# Power.net
KiCad netlist of a schematic drawn in Altium Designer
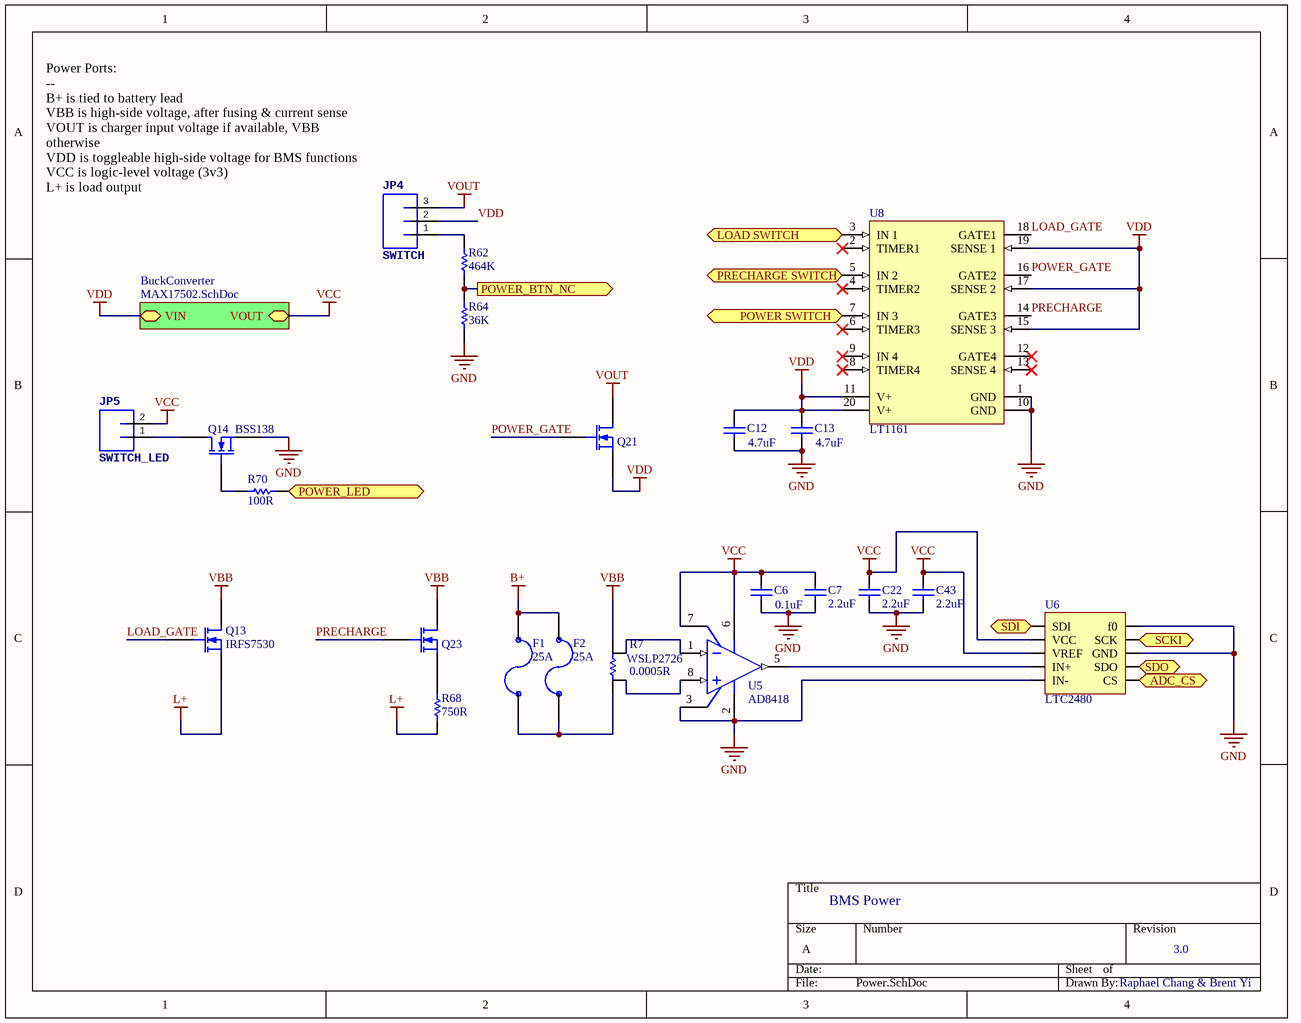
[diagram p0: Power.SchDoc]

(export (version "E")
  (design (tool "Eeschema 10.0.6"))
  (components
    (comp (ref "C6")
      (value "0.1uF")
      (footprint "CAPC0603(1608)55_N")
      (description "CAP 2.2uF 16V Â±10% 0603 (1608 Metric) Thickness 0.55mm SMD")
      (fields (field (name "TOLERANCE") "Â±10%"))
      (libsource (lib "Altium Content Vault") (part "CMP-1035-02762-1"))
    )
    (comp (ref "C7")
      (value "2.2uF")
      (footprint "CAPC0603(1608)100_N")
      (description "CAP 1uF 6.3V Â±10% 0603 (1608 Metric) Thickness 1mm SMD")
      (fields (field (name "TOLERANCE") "Â±10%"))
      (libsource (lib "Altium Content Vault") (part "CMP-1035-02730-1"))
    )
    (comp (ref "C12")
      (value "4.7uF")
      (footprint "CAPC1210(3225)280_N")
      (description "CAP 100uF 10V Â±10% 1210 (3225 Metric) Thickness 2.8mm SMD")
      (fields (field (name "TOLERANCE") "Â±10%"))
      (libsource (lib "Altium Content Vault") (part "CMP-1038-02301-1"))
    )
    (comp (ref "C13")
      (value "4.7uF")
      (footprint "CAPC1210(3225)280_N")
      (description "CAP 100uF 10V Â±10% 1210 (3225 Metric) Thickness 2.8mm SMD")
      (fields (field (name "TOLERANCE") "Â±10%"))
      (libsource (lib "Altium Content Vault") (part "CMP-1038-02301-1"))
    )
    (comp (ref "C22")
      (value "2.2uF")
      (footprint "CAPC0603(1608)55_N")
      (description "CAP 2.2uF 4V Â±10% 0603 (1608 Metric) Thickness 0.55mm SMD")
      (fields (field (name "TOLERANCE") "Â±10%"))
      (libsource (lib "Altium Content Vault") (part "CMP-1035-02751-1"))
    )
    (comp (ref "C43")
      (value "2.2uF")
      (footprint "CAPC0603(1608)55_N")
      (description "CAP 2.2uF 4V Â±10% 0603 (1608 Metric) Thickness 0.55mm SMD")
      (fields (field (name "TOLERANCE") "Â±10%"))
      (libsource (lib "Altium Content Vault") (part "CMP-1035-02751-1"))
    )
    (comp (ref "F1")
      (value "25A")
      (footprint "1206_FUSE")
      (description "Fuse")
      (libsource (lib "Components") (part "FUSE 1206"))
    )
    (comp (ref "F2")
      (value "25A")
      (footprint "1206_FUSE")
      (description "Fuse")
      (libsource (lib "Components") (part "FUSE 1206"))
    )
    (comp (ref "JP4")
      (value "SWITCH")
      (footprint "JST-3-PTH-VERT")
      (libsource (lib "Components") (part "JST_3"))
    )
    (comp (ref "JP5")
      (value "SWITCH_LED")
      (footprint "JST-2-PTH-VERT")
      (libsource (lib "Components") (part "JST_2_VERT"))
    )
    (comp (ref "Q13")
      (value "IRFS7530")
      (footprint "DPAK127P1525X483-7N")
      (description "N-Channel MOSFET")
      (fields (field (name "PUBLISHER") "Altium Limited"))
      (libsource (lib "Components") (part "MOSFET-N"))
    )
    (comp (ref "Q14")
      (value "BSS138")
      (footprint "SOT23-3")
      (description "N-Channel MOSFET")
      (fields (field (name "PUBLISHER") "Altium Limited"))
      (libsource (lib "Components") (part "MOSFET-N"))
    )
    (comp (ref "Q21")
      (value "FDS5672")
      (footprint "SOIC127P600X175-8N")
      (description "N-Channel MOSFET")
      (fields (field (name "PUBLISHER") "Altium Limited"))
      (libsource (lib "Components") (part "MOSFET-N"))
    )
    (comp (ref "Q23")
      (value "BSS138")
      (footprint "SOT23-3")
      (description "N-Channel MOSFET")
      (fields (field (name "PUBLISHER") "Altium Limited"))
      (libsource (lib "Components") (part "MOSFET-N"))
    )
    (comp (ref "R7")
      (value "WSLP2726")
      (footprint "WSL2726")
      (description "Resistor")
      (fields (field (name "ALTIUM_VALUE") "0.0005R") (field (name "PUBLISHER") "Altium Limited"))
      (libsource (lib "Components") (part "WSLP2726"))
    )
    (comp (ref "R62")
      (value "464K")
      (footprint "RESC0603(1608)_L")
      (description "464K 0.1W 1% 0603 (1608 Metric)  SMD")
      (fields (field (name "TOLERANCE") "1 %") (field (name "POWER") "0.1 W"))
      (libsource (lib "Altium Content Vault") (part "CMP-1012-00811-1"))
    )
    (comp (ref "R64")
      (value "36K")
      (footprint "RESC0603(1608)_L")
      (description "36K 0.1W 1% 0603 (1608 Metric)  SMD")
      (fields (field (name "POWER") "0.1 W") (field (name "TOLERANCE") "1 %"))
      (libsource (lib "Altium Content Vault") (part "CMP-1012-00685-1"))
    )
    (comp (ref "R68")
      (value "750R")
      (footprint "RESC2512(6432)_N")
      (description "750R 1W 1% 2512 (6432 Metric)  SMD")
      (fields (field (name "TOLERANCE") "1 %") (field (name "POWER") "1 W"))
      (libsource (lib "Altium Content Vault") (part "RES"))
    )
    (comp (ref "R70")
      (value "100R")
      (footprint "RESC0603(1608)_L")
      (description "100R 0.1W 5% 0603 (1608 Metric)  SMD")
      (fields (field (name "TOLERANCE") "5 %") (field (name "POWER") "0.1 W"))
      (libsource (lib "Altium Content Vault") (part "CMP-1012-00050-1"))
    )
    (comp (ref "U5") (value "AD8418") (footprint "MSOP-8") (libsource (lib "Components") (part "AD8418")))
    (comp (ref "U6") (value "LTC2480") (footprint "MSOP10") (libsource (lib "Components") (part "LTC2480")))
    (comp (ref "U8")
      (value "LT1161")
      (footprint "LT-SW-20_M")
      (fields (field (name "MANUFACTURER") "Linear Technology") (field (name "PARTNUMBER") "LT1161ISW#PBF"))
      (libsource (lib "Altium Inc") (part "LT-LT1161-20"))
    )
  )
  (nets
    (net (code "1") (name "/ADC_CS") (class "Default")
      (node (ref "U6") (pin "9") (pinfunction "CS_9") (pintype "passive"))
    )
    (net (code "2") (name "/LOAD SWITCH") (class "Default")
      (node (ref "U8") (pin "3") (pinfunction "IN_1_3") (pintype "input"))
    )
    (net (code "3") (name "/LOAD_GATE") (class "Default")
      (node (ref "Q13") (pin "1") (pinfunction "G_1") (pintype "passive"))
      (node (ref "U8") (pin "18") (pinfunction "GATE1_18") (pintype "tri_state"))
    )
    (net (code "4") (name "/POWER SWITCH") (class "Default")
      (node (ref "U8") (pin "7") (pinfunction "IN_3_7") (pintype "input"))
    )
    (net (code "5") (name "/POWER_BTN_NC") (class "Default")
      (node (ref "R62") (pin "1") (pinfunction "1_1") (pintype "passive"))
      (node (ref "R64") (pin "2") (pinfunction "2_2") (pintype "passive"))
    )
    (net (code "6") (name "/POWER_GATE") (class "Default")
      (node (ref "Q21") (pin "1") (pinfunction "G_1") (pintype "passive"))
      (node (ref "U8") (pin "16") (pinfunction "GATE2_16") (pintype "tri_state"))
    )
    (net (code "7") (name "/POWER_LED") (class "Default")
      (node (ref "R70") (pin "1") (pinfunction "1_1") (pintype "passive"))
    )
    (net (code "8") (name "/PRECHARGE") (class "Default")
      (node (ref "Q23") (pin "1") (pinfunction "G_1") (pintype "passive"))
      (node (ref "U8") (pin "14") (pinfunction "GATE3_14") (pintype "tri_state"))
    )
    (net (code "9") (name "/PRECHARGE SWITCH") (class "Default")
      (node (ref "U8") (pin "5") (pinfunction "IN_2_5") (pintype "input"))
    )
    (net (code "10") (name "/SCKI") (class "Default")
      (node (ref "U6") (pin "6") (pinfunction "SCK_6") (pintype "passive"))
    )
    (net (code "11") (name "/SDI") (class "Default")
      (node (ref "U6") (pin "0") (pinfunction "SDI_0") (pintype "passive"))
    )
    (net (code "12") (name "/SDO") (class "Default")
      (node (ref "U6") (pin "8") (pinfunction "SDO_8") (pintype "passive"))
    )
    (net (code "13") (name "B+") (class "Default")
      (node (ref "F1") (pin "1") (pinfunction "1_1") (pintype "passive"))
      (node (ref "F2") (pin "1") (pinfunction "1_1") (pintype "passive"))
    )
    (net (code "14") (name "GND") (class "Default")
      (node (ref "C12") (pin "1") (pinfunction "1_1") (pintype "passive"))
      (node (ref "C13") (pin "1") (pinfunction "1_1") (pintype "passive"))
      (node (ref "C22") (pin "1") (pinfunction "1_1") (pintype "passive"))
      (node (ref "C43") (pin "1") (pinfunction "1_1") (pintype "passive"))
      (node (ref "C6") (pin "2") (pinfunction "2_2") (pintype "passive"))
      (node (ref "C7") (pin "2") (pinfunction "2_2") (pintype "passive"))
      (node (ref "Q14") (pin "3") (pinfunction "S_3") (pintype "passive"))
      (node (ref "R64") (pin "1") (pinfunction "1_1") (pintype "passive"))
      (node (ref "U5") (pin "2") (pinfunction "GND_2") (pintype "power_in"))
      (node (ref "U5") (pin "3") (pinfunction "VREF2_3") (pintype "passive"))
      (node (ref "U6") (pin "4") (pinfunction "IN-_4") (pintype "passive"))
      (node (ref "U6") (pin "5") (pinfunction "f0_5") (pintype "passive"))
      (node (ref "U6") (pin "7") (pinfunction "GND_7") (pintype "passive"))
      (node (ref "U8") (pin "1") (pinfunction "GND_1") (pintype "power_in"))
      (node (ref "U8") (pin "10") (pinfunction "GND_10") (pintype "power_in"))
    )
    (net (code "15") (name "L+") (class "Default")
      (node (ref "Q13") (pin "3") (pinfunction "S_3") (pintype "passive"))
      (node (ref "R68") (pin "1") (pinfunction "1_1") (pintype "passive"))
    )
    (net (code "16") (name "Net-(F1-Pad2)") (class "Default")
      (node (ref "F1") (pin "2") (pinfunction "2_2") (pintype "passive"))
      (node (ref "F2") (pin "2") (pinfunction "2_2") (pintype "passive"))
      (node (ref "R7") (pin "1") (pinfunction "1_1") (pintype "passive"))
    )
    (net (code "17") (name "Net-(JP4-Pad1)") (class "Default")
      (node (ref "JP4") (pin "1") (pinfunction "1_1") (pintype "passive"))
      (node (ref "R62") (pin "2") (pinfunction "2_2") (pintype "passive"))
    )
    (net (code "18") (name "Net-(Q14-D)") (class "Default")
      (node (ref "JP5") (pin "1") (pinfunction "1_1") (pintype "passive"))
      (node (ref "Q14") (pin "2") (pinfunction "D_2") (pintype "passive"))
    )
    (net (code "19") (name "Net-(Q14-G)") (class "Default")
      (node (ref "Q14") (pin "1") (pinfunction "G_1") (pintype "passive"))
      (node (ref "R70") (pin "2") (pinfunction "2_2") (pintype "passive"))
    )
    (net (code "20") (name "Net-(Q23-S)") (class "Default")
      (node (ref "Q23") (pin "3") (pinfunction "S_3") (pintype "passive"))
      (node (ref "R68") (pin "2") (pinfunction "2_2") (pintype "passive"))
    )
    (net (code "21") (name "Net-(U5-IN+)") (class "Default")
      (node (ref "R7") (pin "3") (pinfunction "3_3") (pintype "passive"))
      (node (ref "U5") (pin "8") (pinfunction "IN+_8") (pintype "input"))
    )
    (net (code "22") (name "Net-(U5-IN-)") (class "Default")
      (node (ref "R7") (pin "4") (pinfunction "4_4") (pintype "passive"))
      (node (ref "U5") (pin "1") (pinfunction "IN-_1") (pintype "input"))
    )
    (net (code "23") (name "Net-(U5-OUT)") (class "Default")
      (node (ref "U5") (pin "5") (pinfunction "OUT_5") (pintype "output"))
      (node (ref "U6") (pin "3") (pinfunction "IN+_3") (pintype "passive"))
    )
    (net (code "24") (name "VBB") (class "Default")
      (node (ref "Q13") (pin "2") (pinfunction "D_2") (pintype "passive"))
      (node (ref "Q23") (pin "2") (pinfunction "D_2") (pintype "passive"))
      (node (ref "R7") (pin "2") (pinfunction "2_2") (pintype "passive"))
    )
    (net (code "25") (name "VCC") (class "Default")
      (node (ref "C22") (pin "2") (pinfunction "2_2") (pintype "passive"))
      (node (ref "C43") (pin "2") (pinfunction "2_2") (pintype "passive"))
      (node (ref "C6") (pin "1") (pinfunction "1_1") (pintype "passive"))
      (node (ref "C7") (pin "1") (pinfunction "1_1") (pintype "passive"))
      (node (ref "JP5") (pin "2") (pinfunction "2_2") (pintype "passive"))
      (node (ref "U5") (pin "6") (pinfunction "VS_6") (pintype "power_in"))
      (node (ref "U5") (pin "7") (pinfunction "VREF1_7") (pintype "passive"))
      (node (ref "U6") (pin "1") (pinfunction "VCC_1") (pintype "passive"))
      (node (ref "U6") (pin "2") (pinfunction "VREF_2") (pintype "passive"))
    )
    (net (code "26") (name "VDD") (class "Default")
      (node (ref "C12") (pin "2") (pinfunction "2_2") (pintype "passive"))
      (node (ref "C13") (pin "2") (pinfunction "2_2") (pintype "passive"))
      (node (ref "JP4") (pin "2") (pinfunction "2_2") (pintype "passive"))
      (node (ref "Q21") (pin "3") (pinfunction "S_3") (pintype "passive"))
      (node (ref "U8") (pin "11") (pinfunction "V+_11") (pintype "power_in"))
      (node (ref "U8") (pin "15") (pinfunction "SENSE_3_15") (pintype "input"))
      (node (ref "U8") (pin "17") (pinfunction "SENSE_2_17") (pintype "input"))
      (node (ref "U8") (pin "19") (pinfunction "SENSE_1_19") (pintype "input"))
      (node (ref "U8") (pin "20") (pinfunction "V+_20") (pintype "power_in"))
    )
    (net (code "27") (name "VOUT") (class "Default")
      (node (ref "JP4") (pin "3") (pinfunction "3_3") (pintype "passive"))
      (node (ref "Q21") (pin "2") (pinfunction "D_2") (pintype "passive"))
    )
    (net (code "28") (name "unconnected-(U8-GATE4-Pad12)") (class "Default")
      (node (ref "U8") (pin "12") (pinfunction "GATE4_12") (pintype "tri_state+no_connect"))
    )
    (net (code "29") (name "unconnected-(U8-IN_4-Pad9)") (class "Default")
      (node (ref "U8") (pin "9") (pinfunction "IN_4_9") (pintype "input+no_connect"))
    )
    (net (code "30") (name "unconnected-(U8-SENSE_4-Pad13)") (class "Default")
      (node (ref "U8") (pin "13") (pinfunction "SENSE_4_13") (pintype "input+no_connect"))
    )
    (net (code "31") (name "unconnected-(U8-TIMER1-Pad2)") (class "Default")
      (node (ref "U8") (pin "2") (pinfunction "TIMER1_2") (pintype "input+no_connect"))
    )
    (net (code "32") (name "unconnected-(U8-TIMER2-Pad4)") (class "Default")
      (node (ref "U8") (pin "4") (pinfunction "TIMER2_4") (pintype "input+no_connect"))
    )
    (net (code "33") (name "unconnected-(U8-TIMER3-Pad6)") (class "Default")
      (node (ref "U8") (pin "6") (pinfunction "TIMER3_6") (pintype "input+no_connect"))
    )
    (net (code "34") (name "unconnected-(U8-TIMER4-Pad8)") (class "Default")
      (node (ref "U8") (pin "8") (pinfunction "TIMER4_8") (pintype "input+no_connect"))
    )
  )
)
